# ESP12F.net
KiCad netlist of a schematic drawn in Altium Designer
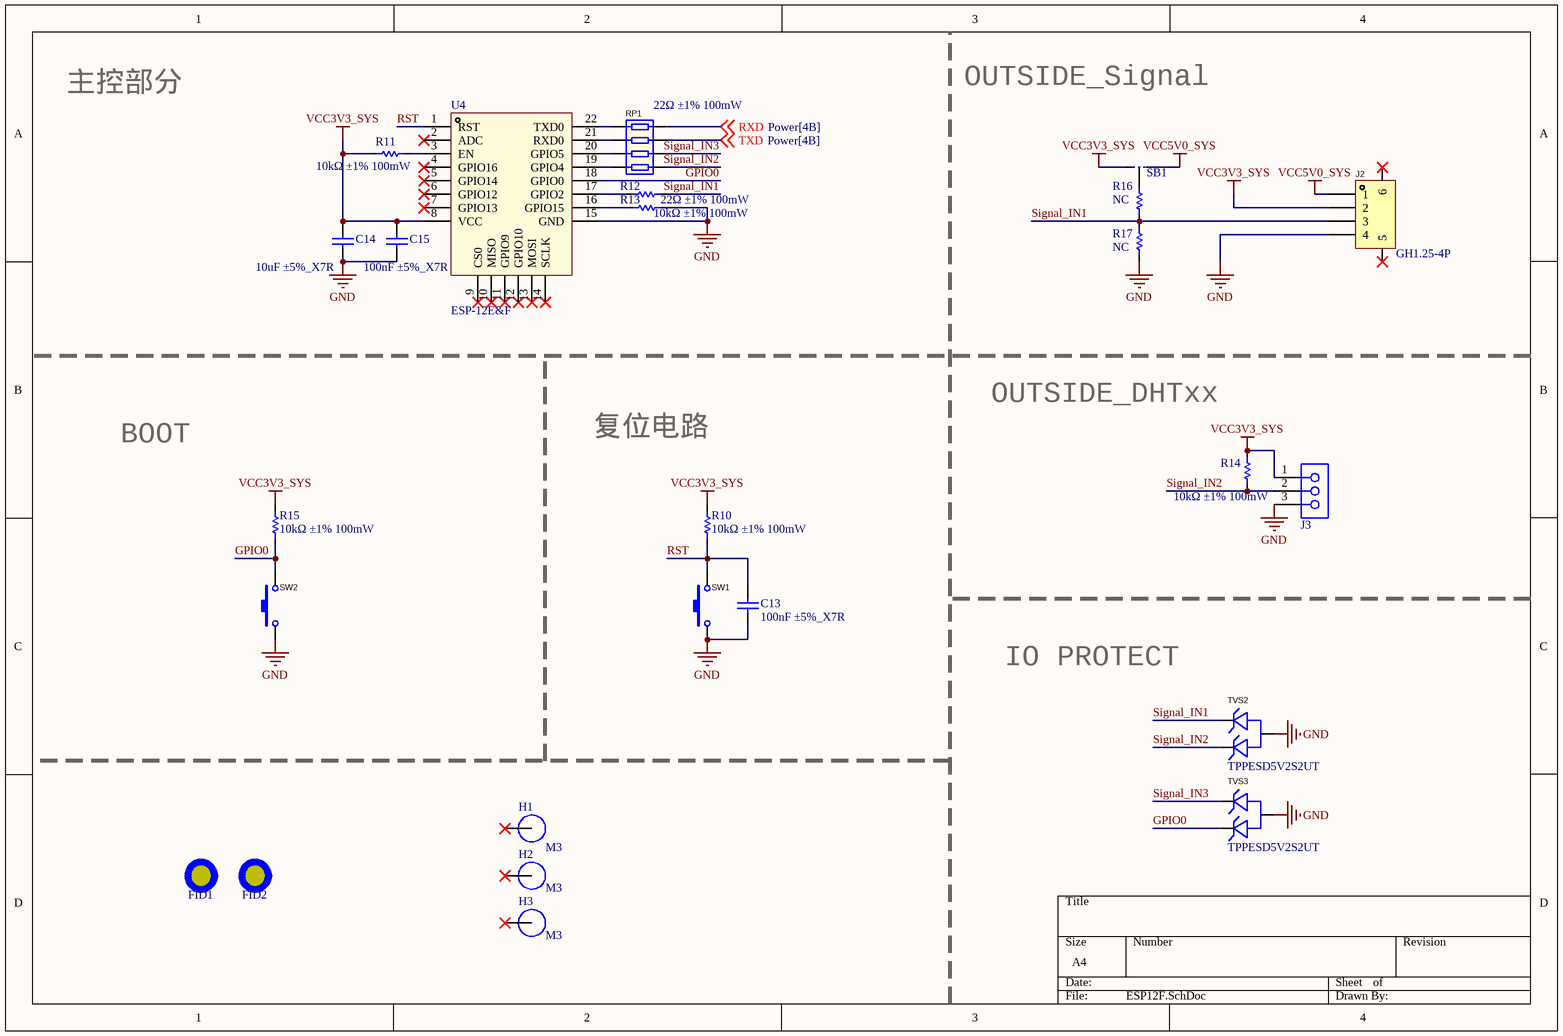
[diagram p0: ESP12F.SchDoc]

(export (version "E")
  (design (tool "Eeschema 10.0.6"))
  (components
    (comp (ref "C13")
      (value "100nF ±5%_X7R")
      (footprint "C0603")
      (description "Capacitor")
      (fields (field (name "PUBLISHER") "Altium Limited"))
      (libsource (lib "Component_Footprints") (part "Cap"))
    )
    (comp (ref "C14")
      (value "10uF ±5%_X7R")
      (footprint "C0603")
      (description "Capacitor")
      (fields (field (name "PUBLISHER") "Altium Limited"))
      (libsource (lib "Component_Footprints") (part "Cap"))
    )
    (comp (ref "C15")
      (value "100nF ±5%_X7R")
      (footprint "C0603")
      (description "Capacitor")
      (fields (field (name "PUBLISHER") "Altium Limited"))
      (libsource (lib "Component_Footprints") (part "Cap"))
    )
    (comp (ref "FID1")
      (value "MARK Point")
      (footprint "FIDUCIAL")
      (description "1mm Fiducial with 2mm soldermask, 3mm keepout")
      (libsource (lib "Component") (part "FIDUCIAL"))
    )
    (comp (ref "FID2")
      (value "MARK Point")
      (footprint "FIDUCIAL")
      (description "1mm Fiducial with 2mm soldermask, 3mm keepout")
      (libsource (lib "Component") (part "FIDUCIAL"))
    )
    (comp (ref "H1")
      (value "M3")
      (footprint "M3_PTH")
      (description "Hole with copper")
      (libsource (lib "Component") (part "PTH"))
    )
    (comp (ref "H2")
      (value "M3")
      (footprint "M3_PTH")
      (description "Hole with copper")
      (libsource (lib "Component") (part "PTH"))
    )
    (comp (ref "H3")
      (value "M3")
      (footprint "M3_PTH")
      (description "Hole with copper")
      (libsource (lib "Component") (part "PTH"))
    )
    (comp (ref "J2")
      (value "GH1.25-4P")
      (footprint "GH1.25-4P")
      (fields
        (field (name "MANUFACTURER") "BOOMELE(博穆精密)")
        (field (name "MANUFACTURER PART") "GH1.25-5PLTPZ")
      )
      (libsource (lib "Connectivity_Plugs") (part "GH1.25-4P"))
    )
    (comp (ref "J3")
      (value "61300311821")
      (footprint "61300311821")
      (description "WR-PHD Socket Header, THT, Vertical, pitch 2.54mm, 1 Row, 3P")
      (fields (field (name "MANUFACTURER") "Wurth Elektronik"))
      (libsource (lib "Altium_WR-PHD (rev22b)") (part "61300311821"))
    )
    (comp (ref "R10")
      (value "10kΩ ±1% 100mW")
      (footprint "R0402")
      (description "Resistor")
      (fields (field (name "PUBLISHER") "Altium Limited"))
      (libsource (lib "Component_Footprints") (part "Res"))
    )
    (comp (ref "R11")
      (value "10kΩ ±1% 100mW")
      (footprint "R0402")
      (description "Resistor")
      (fields (field (name "PUBLISHER") "Altium Limited"))
      (libsource (lib "Component") (part "Res"))
    )
    (comp (ref "R12")
      (value "22Ω ±1% 100mW")
      (footprint "R0402")
      (description "Resistor")
      (fields (field (name "PUBLISHER") "Altium Limited"))
      (libsource (lib "Component") (part "Res"))
    )
    (comp (ref "R13")
      (value "10kΩ ±1% 100mW")
      (footprint "R0402")
      (description "Resistor")
      (fields (field (name "PUBLISHER") "Altium Limited"))
      (libsource (lib "Component") (part "Res"))
    )
    (comp (ref "R14")
      (value "10kΩ ±1% 100mW")
      (footprint "R0402")
      (description "Resistor")
      (fields (field (name "PUBLISHER") "Altium Limited"))
      (libsource (lib "Component_Footprints") (part "Res"))
    )
    (comp (ref "R15")
      (value "10kΩ ±1% 100mW")
      (footprint "R0402")
      (description "Resistor")
      (fields (field (name "PUBLISHER") "Altium Limited"))
      (libsource (lib "Component_Footprints") (part "Res"))
    )
    (comp (ref "R16")
      (value "NC")
      (footprint "R0402")
      (description "Resistor")
      (fields (field (name "PUBLISHER") "Altium Limited"))
      (libsource (lib "Component_Footprints") (part "Res"))
    )
    (comp (ref "R17")
      (value "NC")
      (footprint "R0402")
      (description "Resistor")
      (fields (field (name "PUBLISHER") "Altium Limited"))
      (libsource (lib "Component_Footprints") (part "Res"))
    )
    (comp (ref "RP1")
      (value "22Ω ±1% 100mW")
      (footprint "RES-ARRAY-SMD_0603-8P-L3.2-W1.6-BL")
      (fields
        (field (name "MANUFACTURER") "YAGEO(国巨)")
        (field (name "MANUFACTURER PART") "YC124-JR-0730RL")
        (field (name "TOLERANCE") "±5%")
      )
      (libsource (lib "Component_Footprints") (part "RP"))
    )
    (comp (ref "SB1")
      (value "SHORT_3")
      (footprint "SHORT_3_180deg")
      (libsource (lib "Component") (part "SHORT_3"))
    )
    (comp (ref "SW1")
      (value "TS-1185-B-A-B-A")
      (footprint "SW-SMD_L4.0-W3.0-LS5.0")
      (description "触点电流：50mA 额定电压(DC)：12V 电路结构：单刀单掷 安装方式：立贴 带灯：无 作用力：160gf 机械寿命：10万次 带支架：否 轻触开关3x4x2贴片2脚小龟 160gf")
      (fields (field (name "MANUFACTURER") "XKB Connectivity(中国星坤)"))
      (libsource (lib "Component_Footprints") (part "Button"))
    )
    (comp (ref "SW2")
      (value "TS-1185-B-A-B-A")
      (footprint "SW-SMD_L4.0-W3.0-LS5.0")
      (description "触点电流：50mA 额定电压(DC)：12V 电路结构：单刀单掷 安装方式：立贴 带灯：无 作用力：160gf 机械寿命：10万次 带支架：否 轻触开关3x4x2贴片2脚小龟 160gf")
      (fields (field (name "MANUFACTURER") "XKB Connectivity(中国星坤)"))
      (libsource (lib "Component_Footprints") (part "Button"))
    )
    (comp (ref "TVS2")
      (value "TPPESD5V2S2UT")
      (footprint "SOT-23-3_L2.9-W1.3-P1.90-LS2.4-BR")
      (fields (field (name "MANUFACTURER") "TECH PUBLIC(台舟)"))
      (libsource (lib "Component") (part "TVS"))
    )
    (comp (ref "TVS3")
      (value "TPPESD5V2S2UT")
      (footprint "SOT-23-3_L2.9-W1.3-P1.90-LS2.4-BR")
      (fields (field (name "MANUFACTURER") "TECH PUBLIC(台舟)"))
      (libsource (lib "Component") (part "TVS"))
    )
    (comp (ref "U4")
      (value "ESP-12E&F")
      (footprint "ESP-12E")
      (description "ESP-12E&F Onboard Module")
      (libsource (lib "Common_Modules") (part "ESP-12E&F"))
    )
  )
  (nets
    (net (code "1") (name "/GPIO0") (class "Default")
      (node (ref "R15") (pin "1") (pinfunction "1_1") (pintype "passive"))
      (node (ref "SW2") (pin "2") (pinfunction "2_2") (pintype "passive"))
      (node (ref "TVS3") (pin "1") (pinfunction "A_1") (pintype "passive"))
      (node (ref "U4") (pin "18") (pinfunction "GPIO0_18") (pintype "passive"))
    )
    (net (code "2") (name "/RST") (class "Default")
      (node (ref "C13") (pin "2") (pinfunction "2_2") (pintype "passive"))
      (node (ref "R10") (pin "1") (pinfunction "1_1") (pintype "passive"))
      (node (ref "SW1") (pin "2") (pinfunction "2_2") (pintype "passive"))
      (node (ref "U4") (pin "1") (pinfunction "RST_1") (pintype "passive"))
    )
    (net (code "3") (name "/Signal_IN1") (class "Default")
      (node (ref "J2") (pin "3") (pinfunction "3_3") (pintype "passive"))
      (node (ref "R12") (pin "2") (pinfunction "2_2") (pintype "passive"))
      (node (ref "R16") (pin "1") (pinfunction "1_1") (pintype "passive"))
      (node (ref "R17") (pin "2") (pinfunction "2_2") (pintype "passive"))
      (node (ref "TVS2") (pin "2") (pinfunction "A_2") (pintype "passive"))
    )
    (net (code "4") (name "/Signal_IN2") (class "Default")
      (node (ref "J3") (pin "2") (pinfunction "2_2") (pintype "passive"))
      (node (ref "R14") (pin "1") (pinfunction "1_1") (pintype "passive"))
      (node (ref "RP1") (pin "1") (pinfunction "1_1") (pintype "passive"))
      (node (ref "TVS2") (pin "1") (pinfunction "A_1") (pintype "passive"))
    )
    (net (code "5") (name "/Signal_IN3") (class "Default")
      (node (ref "RP1") (pin "2") (pinfunction "2_2") (pintype "passive"))
      (node (ref "TVS3") (pin "2") (pinfunction "A_2") (pintype "passive"))
    )
    (net (code "6") (name "GND") (class "Default")
      (node (ref "C13") (pin "1") (pinfunction "1_1") (pintype "passive"))
      (node (ref "C14") (pin "1") (pinfunction "1_1") (pintype "passive"))
      (node (ref "C15") (pin "1") (pinfunction "1_1") (pintype "passive"))
      (node (ref "J2") (pin "4") (pinfunction "4_4") (pintype "passive"))
      (node (ref "J3") (pin "3") (pinfunction "3_3") (pintype "passive"))
      (node (ref "R13") (pin "2") (pinfunction "2_2") (pintype "passive"))
      (node (ref "R17") (pin "1") (pinfunction "1_1") (pintype "passive"))
      (node (ref "SW1") (pin "1") (pinfunction "1_1") (pintype "passive"))
      (node (ref "SW2") (pin "1") (pinfunction "1_1") (pintype "passive"))
      (node (ref "TVS2") (pin "3") (pinfunction "K_3") (pintype "passive"))
      (node (ref "TVS3") (pin "3") (pinfunction "K_3") (pintype "passive"))
      (node (ref "U4") (pin "15") (pinfunction "GND_15") (pintype "passive"))
    )
    (net (code "7") (name "Net-(R16-Pad2)") (class "Default")
      (node (ref "R16") (pin "2") (pinfunction "2_2") (pintype "passive"))
      (node (ref "SB1") (pin "3") (pinfunction "3_3") (pintype "passive"))
    )
    (net (code "8") (name "Net-(U4-EN)") (class "Default")
      (node (ref "R11") (pin "2") (pinfunction "2_2") (pintype "passive"))
      (node (ref "U4") (pin "3") (pinfunction "EN_3") (pintype "passive"))
    )
    (net (code "9") (name "Net-(U4-GPIO2)") (class "Default")
      (node (ref "R12") (pin "1") (pinfunction "1_1") (pintype "passive"))
      (node (ref "U4") (pin "17") (pinfunction "GPIO2_17") (pintype "passive"))
    )
    (net (code "10") (name "Net-(U4-GPIO4)") (class "Default")
      (node (ref "RP1") (pin "8") (pinfunction "8_8") (pintype "passive"))
      (node (ref "U4") (pin "19") (pinfunction "GPIO4_19") (pintype "passive"))
    )
    (net (code "11") (name "Net-(U4-GPIO5)") (class "Default")
      (node (ref "RP1") (pin "7") (pinfunction "7_7") (pintype "passive"))
      (node (ref "U4") (pin "20") (pinfunction "GPIO5_20") (pintype "passive"))
    )
    (net (code "12") (name "Net-(U4-GPIO15)") (class "Default")
      (node (ref "R13") (pin "1") (pinfunction "1_1") (pintype "passive"))
      (node (ref "U4") (pin "16") (pinfunction "GPIO15_16") (pintype "passive"))
    )
    (net (code "13") (name "Net-(U4-RXD0)") (class "Default")
      (node (ref "RP1") (pin "6") (pinfunction "6_6") (pintype "passive"))
      (node (ref "U4") (pin "21") (pinfunction "RXD0_21") (pintype "passive"))
    )
    (net (code "14") (name "Net-(U4-TXD0)") (class "Default")
      (node (ref "RP1") (pin "5") (pinfunction "5_5") (pintype "passive"))
      (node (ref "U4") (pin "22") (pinfunction "TXD0_22") (pintype "passive"))
    )
    (net (code "15") (name "RXD") (class "Default")
      (node (ref "RP1") (pin "4") (pinfunction "4_4") (pintype "passive"))
    )
    (net (code "16") (name "TXD") (class "Default")
      (node (ref "RP1") (pin "3") (pinfunction "3_3") (pintype "passive"))
    )
    (net (code "17") (name "VCC3V3_SYS") (class "Default")
      (node (ref "C14") (pin "2") (pinfunction "2_2") (pintype "passive"))
      (node (ref "C15") (pin "2") (pinfunction "2_2") (pintype "passive"))
      (node (ref "J2") (pin "2") (pinfunction "2_2") (pintype "passive"))
      (node (ref "J3") (pin "1") (pinfunction "1_1") (pintype "passive"))
      (node (ref "R10") (pin "2") (pinfunction "2_2") (pintype "passive"))
      (node (ref "R11") (pin "1") (pinfunction "1_1") (pintype "passive"))
      (node (ref "R14") (pin "2") (pinfunction "2_2") (pintype "passive"))
      (node (ref "R15") (pin "2") (pinfunction "2_2") (pintype "passive"))
      (node (ref "SB1") (pin "1") (pinfunction "1_1") (pintype "passive"))
      (node (ref "U4") (pin "8") (pinfunction "VCC_8") (pintype "passive"))
    )
    (net (code "18") (name "VCC5V0_SYS") (class "Default")
      (node (ref "J2") (pin "1") (pinfunction "1_1") (pintype "passive"))
      (node (ref "SB1") (pin "2") (pinfunction "2_2") (pintype "passive"))
    )
    (net (code "19") (name "unconnected-(H1-Pad1)") (class "Default")
      (node (ref "H1") (pin "1") (pinfunction "1_1") (pintype "passive+no_connect"))
    )
    (net (code "20") (name "unconnected-(H2-Pad1)") (class "Default")
      (node (ref "H2") (pin "1") (pinfunction "1_1") (pintype "passive+no_connect"))
    )
    (net (code "21") (name "unconnected-(H3-Pad1)") (class "Default")
      (node (ref "H3") (pin "1") (pinfunction "1_1") (pintype "passive+no_connect"))
    )
    (net (code "22") (name "unconnected-(J2-Pad5)") (class "Default")
      (node (ref "J2") (pin "5") (pinfunction "5_5") (pintype "passive+no_connect"))
    )
    (net (code "23") (name "unconnected-(J2-Pad6)") (class "Default")
      (node (ref "J2") (pin "6") (pinfunction "6_6") (pintype "passive+no_connect"))
    )
    (net (code "24") (name "unconnected-(U4-ADC-Pad2)") (class "Default")
      (node (ref "U4") (pin "2") (pinfunction "ADC_2") (pintype "passive+no_connect"))
    )
    (net (code "25") (name "unconnected-(U4-CS0-Pad9)") (class "Default")
      (node (ref "U4") (pin "9") (pinfunction "CS0_9") (pintype "passive+no_connect"))
    )
    (net (code "26") (name "unconnected-(U4-GPIO9-Pad11)") (class "Default")
      (node (ref "U4") (pin "11") (pinfunction "GPIO9_11") (pintype "passive+no_connect"))
    )
    (net (code "27") (name "unconnected-(U4-GPIO10-Pad12)") (class "Default")
      (node (ref "U4") (pin "12") (pinfunction "GPIO10_12") (pintype "passive+no_connect"))
    )
    (net (code "28") (name "unconnected-(U4-GPIO12-Pad6)") (class "Default")
      (node (ref "U4") (pin "6") (pinfunction "GPIO12_6") (pintype "passive+no_connect"))
    )
    (net (code "29") (name "unconnected-(U4-GPIO13-Pad7)") (class "Default")
      (node (ref "U4") (pin "7") (pinfunction "GPIO13_7") (pintype "passive+no_connect"))
    )
    (net (code "30") (name "unconnected-(U4-GPIO14-Pad5)") (class "Default")
      (node (ref "U4") (pin "5") (pinfunction "GPIO14_5") (pintype "passive+no_connect"))
    )
    (net (code "31") (name "unconnected-(U4-GPIO16-Pad4)") (class "Default")
      (node (ref "U4") (pin "4") (pinfunction "GPIO16_4") (pintype "passive+no_connect"))
    )
    (net (code "32") (name "unconnected-(U4-MISO-Pad10)") (class "Default")
      (node (ref "U4") (pin "10") (pinfunction "MISO_10") (pintype "passive+no_connect"))
    )
    (net (code "33") (name "unconnected-(U4-MOSI-Pad13)") (class "Default")
      (node (ref "U4") (pin "13") (pinfunction "MOSI_13") (pintype "passive+no_connect"))
    )
    (net (code "34") (name "unconnected-(U4-SCLK-Pad14)") (class "Default")
      (node (ref "U4") (pin "14") (pinfunction "SCLK_14") (pintype "passive+no_connect"))
    )
  )
)
